# STM32_learning_stand.net
KiCad netlist of a schematic drawn in EAGLE
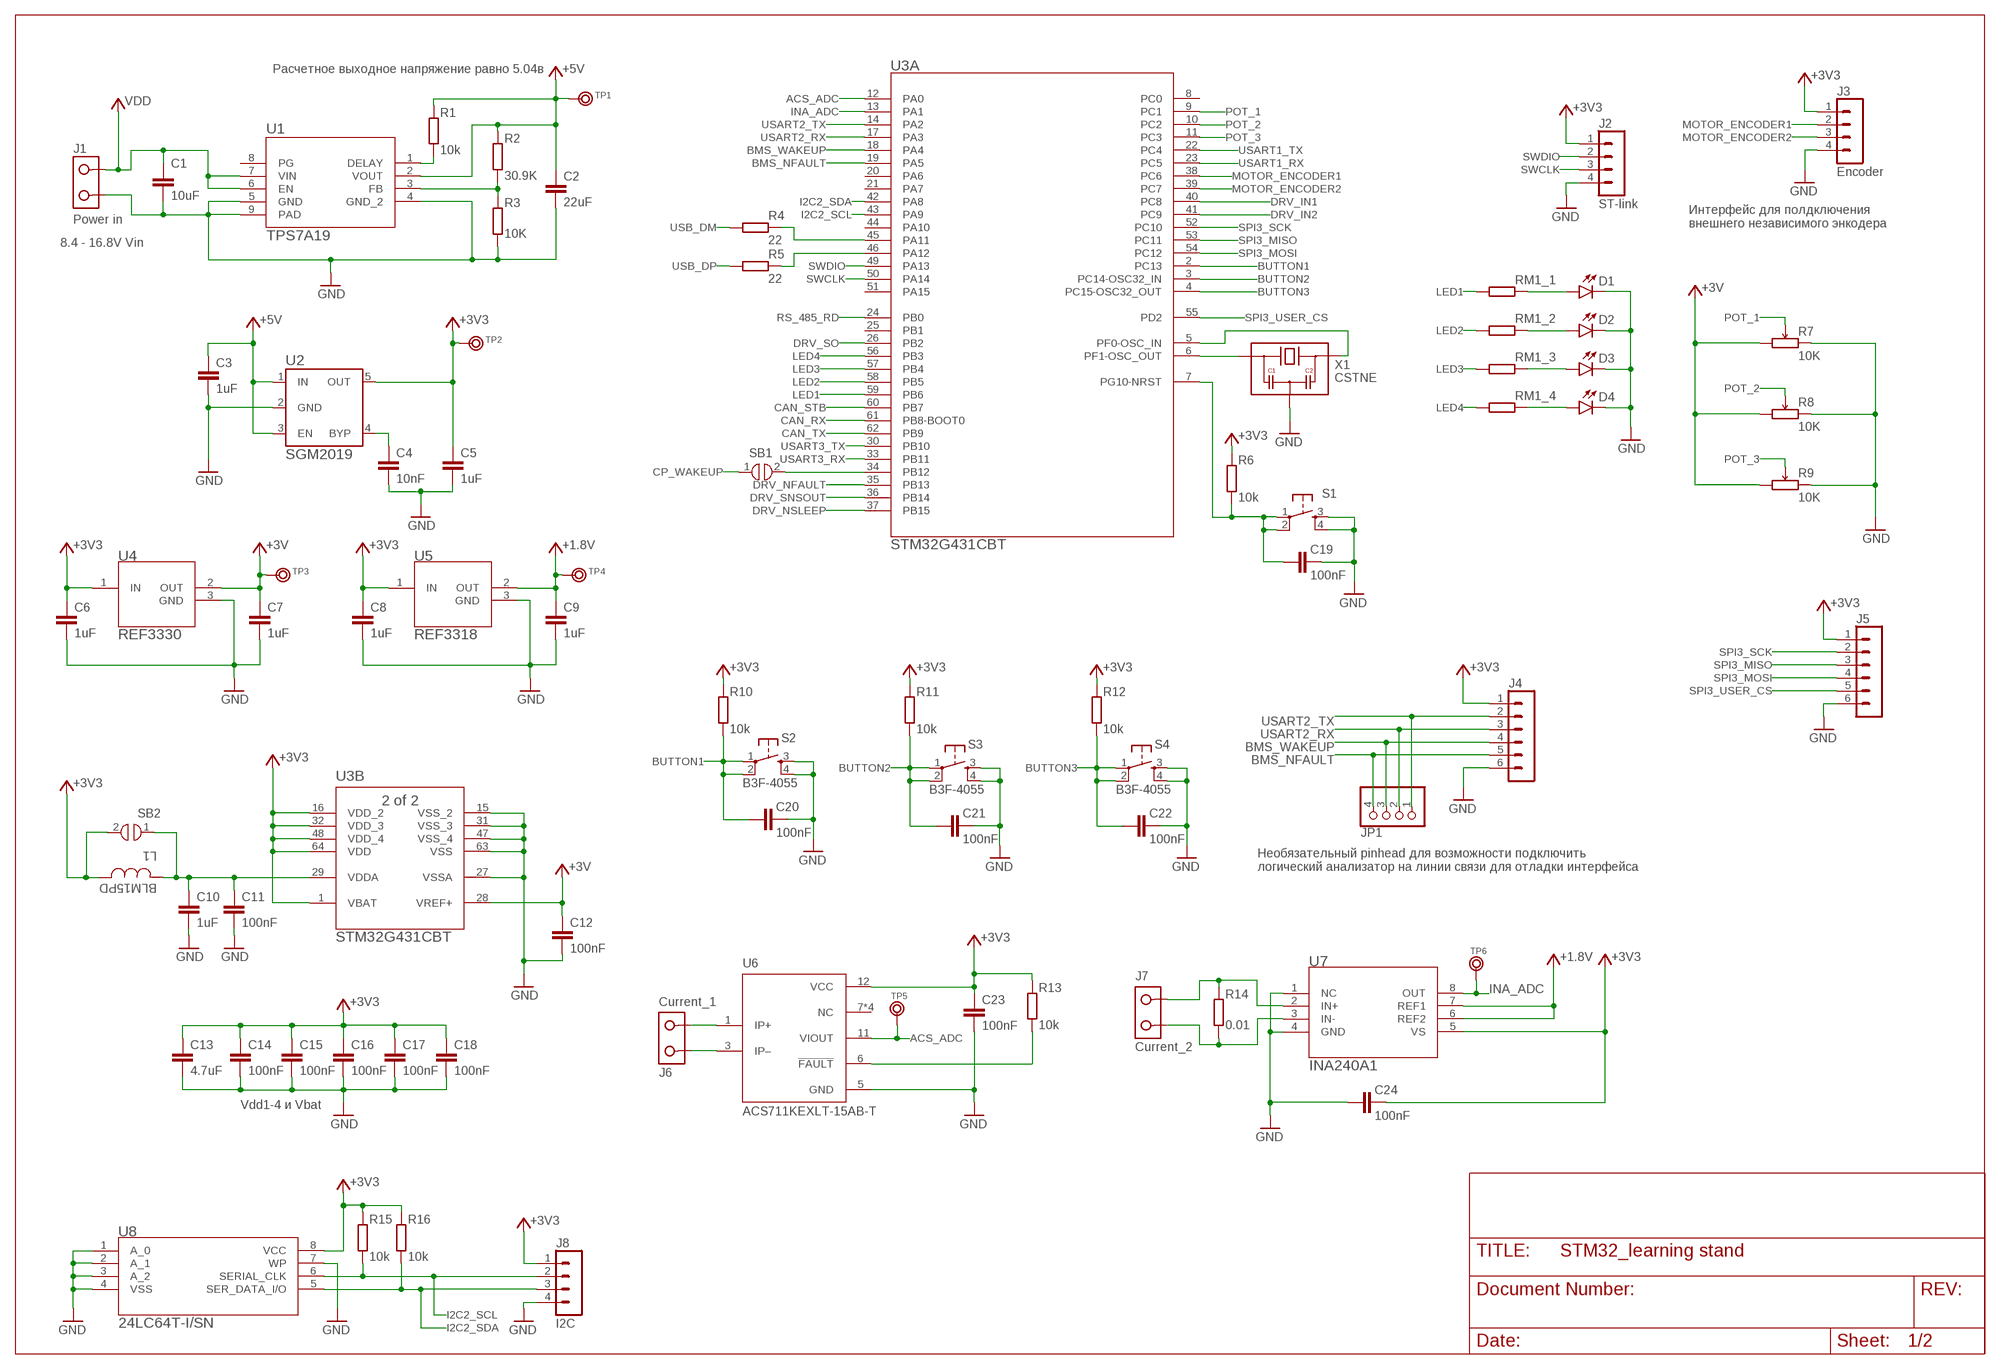
[diagram p0: schematic, sheet 1]
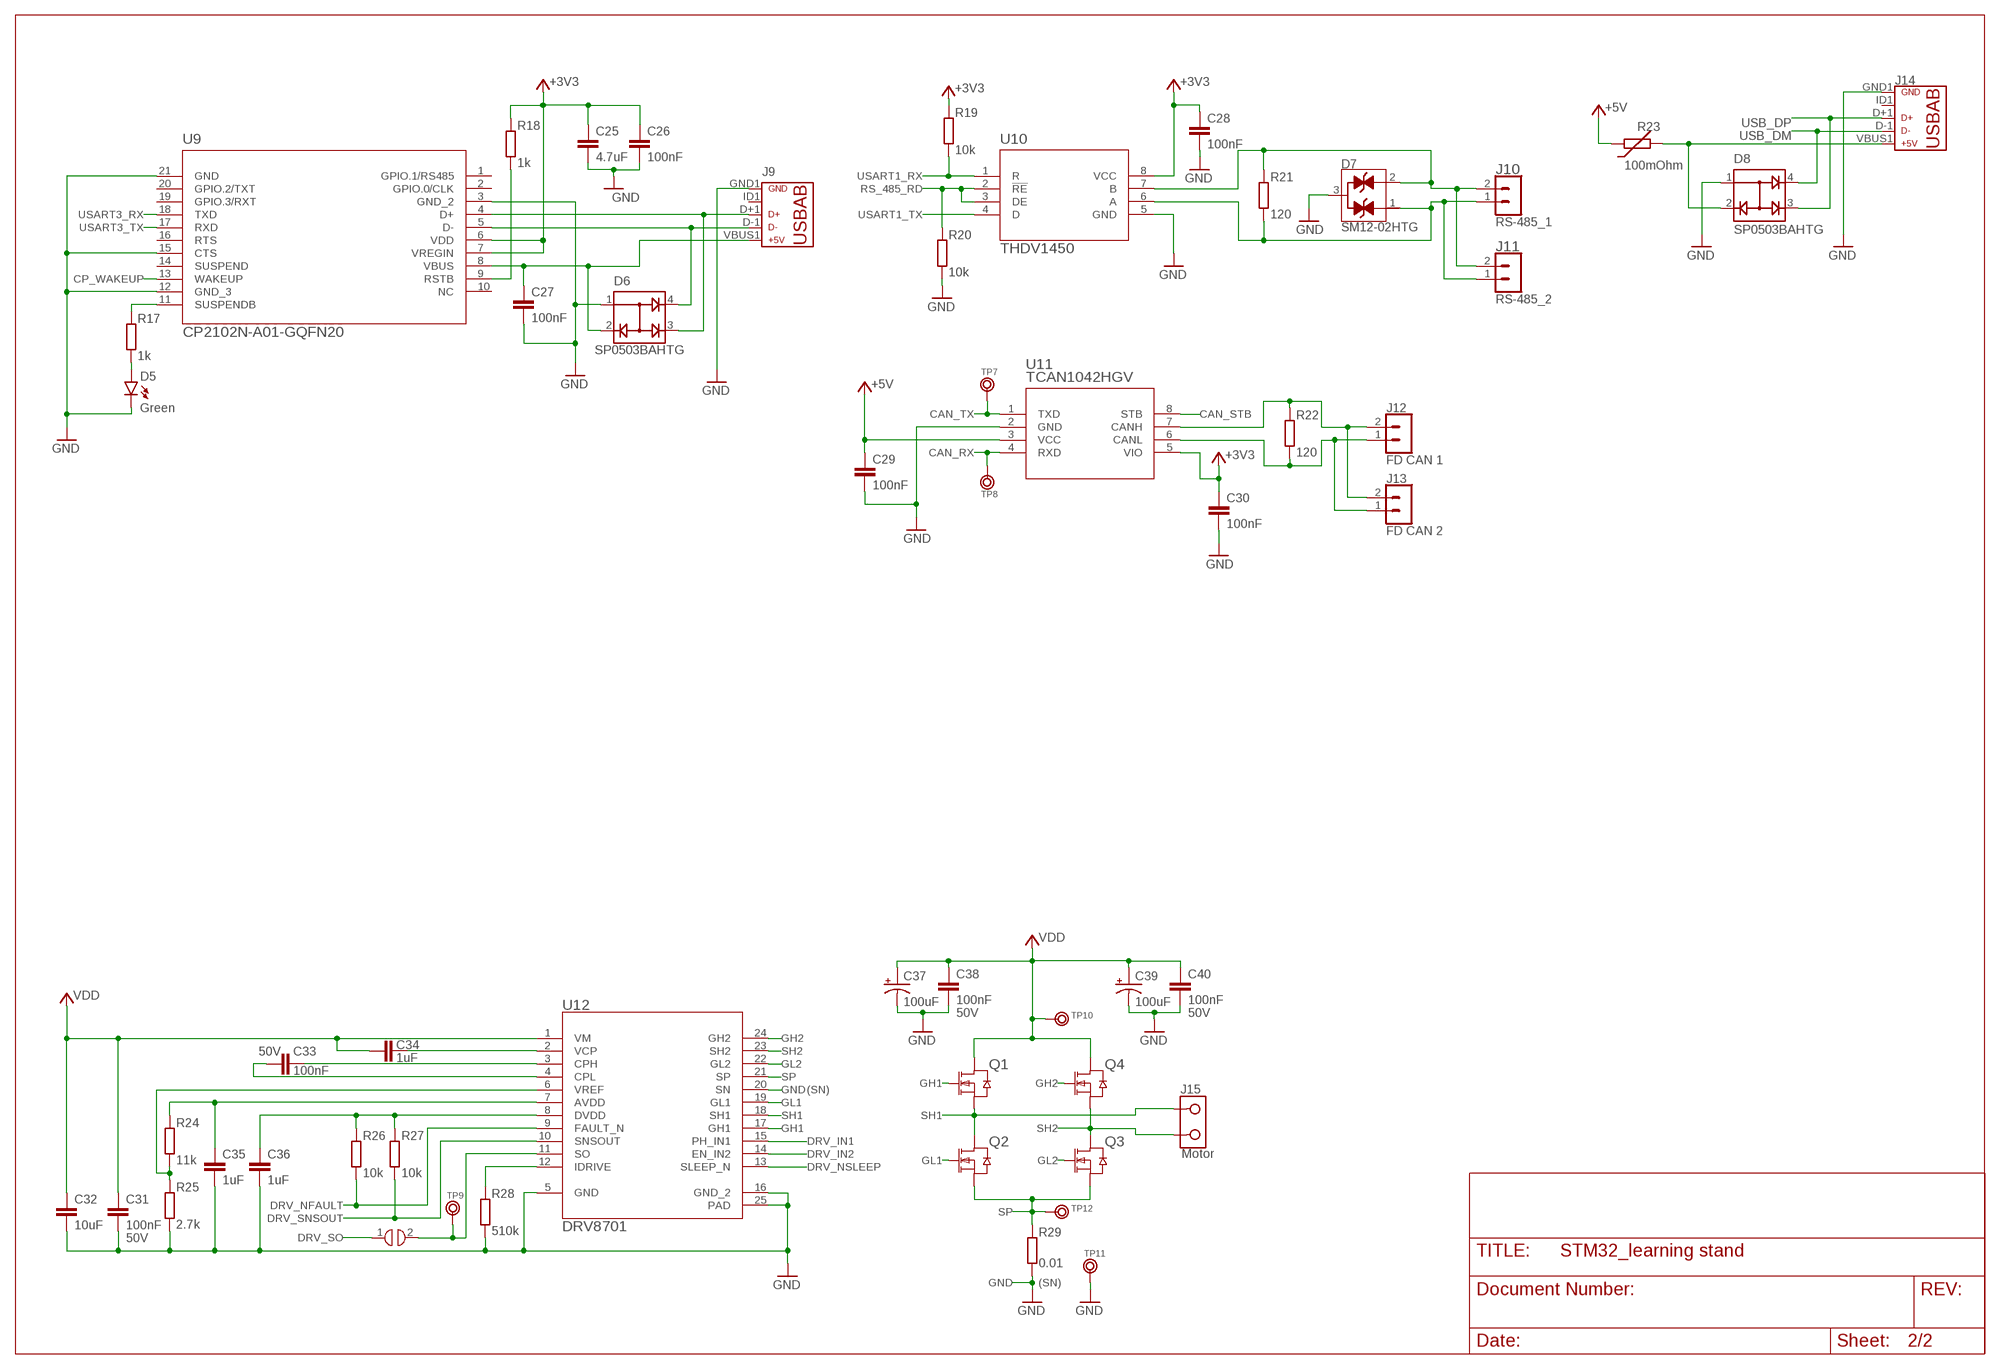
[diagram p1: schematic, sheet 2]

(export (version "E")
  (design (tool "Eeschema 10.0.6"))
  (components
    (comp (ref "C25")
      (value "4.7uF")
      (footprint "eagle-import:C0603")
      (libsource (lib "eagle-import") (part "C-EU0603"))
    )
    (comp (ref "C26")
      (value "100nF")
      (footprint "eagle-import:C0402")
      (libsource (lib "eagle-import") (part "C-EU0402"))
    )
    (comp (ref "C27")
      (value "100nF")
      (footprint "eagle-import:C0402")
      (libsource (lib "eagle-import") (part "C-EU0402"))
    )
    (comp (ref "C28")
      (value "100nF")
      (footprint "eagle-import:C0402")
      (libsource (lib "eagle-import") (part "C-EU0402"))
    )
    (comp (ref "C29")
      (value "100nF")
      (footprint "eagle-import:C0402")
      (libsource (lib "eagle-import") (part "C-EU0402"))
    )
    (comp (ref "C30")
      (value "100nF")
      (footprint "eagle-import:C0402")
      (libsource (lib "eagle-import") (part "C-EU0402"))
    )
    (comp (ref "C31")
      (value "100nF")
      (footprint "eagle-import:C0603")
      (libsource (lib "eagle-import") (part "C-EU-CERAMIC0603"))
    )
    (comp (ref "C32")
      (value "10uF")
      (footprint "eagle-import:C1206")
      (libsource (lib "eagle-import") (part "C-EU1206"))
    )
    (comp (ref "C33")
      (value "100nF")
      (footprint "eagle-import:C0603")
      (libsource (lib "eagle-import") (part "C-EU-CERAMIC0603"))
    )
    (comp (ref "C34")
      (value "1uF")
      (footprint "eagle-import:C0603")
      (libsource (lib "eagle-import") (part "C-EU0603"))
    )
    (comp (ref "C35")
      (value "1uF")
      (footprint "eagle-import:C0603")
      (libsource (lib "eagle-import") (part "C-EU0603"))
    )
    (comp (ref "C36")
      (value "1uF")
      (footprint "eagle-import:C0603")
      (libsource (lib "eagle-import") (part "C-EU0603"))
    )
    (comp (ref "C37")
      (value "100uF")
      (footprint "eagle-import:6.3X7.7")
      (fields
        (field (name "MANUFACTURER_PART_NUMBER") "EEE-1VA100WAR")
        (field (name "COPYRIGHT") "Copyright (C) 2018 Accelerated Designs. All rights reserved")
      )
      (libsource (lib "eagle-import") (part "C-EU-ELECTROLYTIC-6.3X7.7"))
    )
    (comp (ref "C38")
      (value "100nF")
      (footprint "eagle-import:C0603")
      (libsource (lib "eagle-import") (part "C-EU-CERAMIC0603"))
    )
    (comp (ref "C39")
      (value "100uF")
      (footprint "eagle-import:6.3X7.7")
      (fields
        (field (name "MANUFACTURER_PART_NUMBER") "EEE-1VA100WAR")
        (field (name "COPYRIGHT") "Copyright (C) 2018 Accelerated Designs. All rights reserved")
      )
      (libsource (lib "eagle-import") (part "C-EU-ELECTROLYTIC-6.3X7.7"))
    )
    (comp (ref "C40")
      (value "100nF")
      (footprint "eagle-import:C0603")
      (libsource (lib "eagle-import") (part "C-EU-CERAMIC0603"))
    )
    (comp (ref "D5")
      (value "Green")
      (footprint "eagle-import:LED-0805")
      (libsource (lib "eagle-import") (part "LED0805"))
    )
    (comp (ref "D6")
      (value "SP0503BAHTG")
      (footprint "eagle-import:SOT143")
      (fields (field (name "DIGI-KEY_PART_NUMBER") "F2715CT-ND") (field (name "MF") "Littelfuse Inc."))
      (libsource (lib "eagle-import") (part "SP0503BAHTG"))
    )
    (comp (ref "D7")
      (value "SM12-02HTG")
      (footprint "eagle-import:SOT23")
      (libsource (lib "eagle-import") (part "SOT_23_TVS"))
    )
    (comp (ref "D8")
      (value "SP0503BAHTG")
      (footprint "eagle-import:SOT143")
      (fields (field (name "DIGI-KEY_PART_NUMBER") "F2715CT-ND") (field (name "MF") "Littelfuse Inc."))
      (libsource (lib "eagle-import") (part "SP0503BAHTG"))
    )
    (comp (ref "J9")
      (value "USB_MICRO\"\"")
      (footprint "eagle-import:USB-MICRO-SMD")
      (libsource (lib "eagle-import") (part "USB_MICRO{dblquote}{dblquote}"))
    )
    (comp (ref "J10")
      (value "RS-485_1")
      (footprint "eagle-import:S2B-PH-K")
      (libsource (lib "eagle-import") (part "S2B-PH-K"))
    )
    (comp (ref "J11")
      (value "RS-485_2")
      (footprint "eagle-import:S2B-PH-K")
      (libsource (lib "eagle-import") (part "S2B-PH-K"))
    )
    (comp (ref "J12")
      (value "FD CAN 1")
      (footprint "eagle-import:S2B-PH-K")
      (libsource (lib "eagle-import") (part "S2B-PH-K"))
    )
    (comp (ref "J13")
      (value "FD CAN 2")
      (footprint "eagle-import:S2B-PH-K")
      (libsource (lib "eagle-import") (part "S2B-PH-K"))
    )
    (comp (ref "J14")
      (value "USB_MICRO\"\"")
      (footprint "eagle-import:USB-MICRO-SMD")
      (libsource (lib "eagle-import") (part "USB_MICRO{dblquote}{dblquote}"))
    )
    (comp (ref "J15")
      (value "Motor")
      (footprint "eagle-import:DG301-2P")
      (libsource (lib "eagle-import") (part "DG301-2P{dblquote}"))
    )
    (comp (ref "Q1")
      (value "SON5X6_MOSFET")
      (footprint "eagle-import:SON5X6")
      (fields (field (name "MANUFACTURER_PART_NUMBER") "CSD18534Q5A"))
      (libsource (lib "eagle-import") (part "SON5X6_MOSFET"))
    )
    (comp (ref "Q2")
      (value "SON5X6_MOSFET")
      (footprint "eagle-import:SON5X6")
      (fields (field (name "MANUFACTURER_PART_NUMBER") "CSD18534Q5A"))
      (libsource (lib "eagle-import") (part "SON5X6_MOSFET"))
    )
    (comp (ref "Q3")
      (value "SON5X6_MOSFET")
      (footprint "eagle-import:SON5X6")
      (fields (field (name "MANUFACTURER_PART_NUMBER") "CSD18534Q5A"))
      (libsource (lib "eagle-import") (part "SON5X6_MOSFET"))
    )
    (comp (ref "Q4")
      (value "SON5X6_MOSFET")
      (footprint "eagle-import:SON5X6")
      (fields (field (name "MANUFACTURER_PART_NUMBER") "CSD18534Q5A"))
      (libsource (lib "eagle-import") (part "SON5X6_MOSFET"))
    )
    (comp (ref "R17")
      (value "1k")
      (footprint "eagle-import:R0402")
      (libsource (lib "eagle-import") (part "R-EU0402"))
    )
    (comp (ref "R18")
      (value "1k")
      (footprint "eagle-import:R0402")
      (libsource (lib "eagle-import") (part "R-EU0402"))
    )
    (comp (ref "R19")
      (value "10k")
      (footprint "eagle-import:R0402")
      (libsource (lib "eagle-import") (part "R-EU0402"))
    )
    (comp (ref "R20")
      (value "10k")
      (footprint "eagle-import:R0402")
      (libsource (lib "eagle-import") (part "R-EU0402"))
    )
    (comp (ref "R21")
      (value "120")
      (footprint "eagle-import:R0805")
      (libsource (lib "eagle-import") (part "R-EU0805"))
    )
    (comp (ref "R22")
      (value "120")
      (footprint "eagle-import:R0805")
      (libsource (lib "eagle-import") (part "R-EU0805"))
    )
    (comp (ref "R23")
      (value "100mOhm")
      (footprint "eagle-import:0805_PTC_FUSE")
      (libsource (lib "eagle-import") (part "PTC_FUSE-0805"))
    )
    (comp (ref "R24")
      (value "11k")
      (footprint "eagle-import:R0402")
      (libsource (lib "eagle-import") (part "R-EU0402"))
    )
    (comp (ref "R25")
      (value "2.7k")
      (footprint "eagle-import:R0402")
      (libsource (lib "eagle-import") (part "R-EU0402"))
    )
    (comp (ref "R26")
      (value "10k")
      (footprint "eagle-import:R0402")
      (libsource (lib "eagle-import") (part "R-EU0402"))
    )
    (comp (ref "R27")
      (value "10k")
      (footprint "eagle-import:R0402")
      (libsource (lib "eagle-import") (part "R-EU0402"))
    )
    (comp (ref "R28")
      (value "510k")
      (footprint "eagle-import:R0402")
      (libsource (lib "eagle-import") (part "R-EU0402"))
    )
    (comp (ref "R29")
      (value "0.01")
      (footprint "eagle-import:CS_R0805")
      (libsource (lib "eagle-import") (part "R_EU_CS"))
    )
    (comp (ref "SB3")
      (value "SOLDER_BRIDGE")
      (footprint "eagle-import:SOLDER_BRIDGE")
      (libsource (lib "eagle-import") (part "SOLDER_BRIDGE"))
    )
    (comp (ref "TP7")
      (value "TEST_RING")
      (footprint "eagle-import:TEST_RING")
      (libsource (lib "eagle-import") (part "TEST_RING"))
    )
    (comp (ref "TP8")
      (value "TEST_RING")
      (footprint "eagle-import:TEST_RING")
      (libsource (lib "eagle-import") (part "TEST_RING"))
    )
    (comp (ref "TP9")
      (value "TEST_RING")
      (footprint "eagle-import:TEST_RING")
      (libsource (lib "eagle-import") (part "TEST_RING"))
    )
    (comp (ref "TP10")
      (value "TEST_RING")
      (footprint "eagle-import:TEST_RING")
      (libsource (lib "eagle-import") (part "TEST_RING"))
    )
    (comp (ref "TP11")
      (value "TEST_RING")
      (footprint "eagle-import:TEST_RING")
      (libsource (lib "eagle-import") (part "TEST_RING"))
    )
    (comp (ref "TP12")
      (value "TEST_RING")
      (footprint "eagle-import:TEST_RING")
      (libsource (lib "eagle-import") (part "TEST_RING"))
    )
    (comp (ref "U9")
      (value "CP2102N-A01-GQFN20")
      (footprint "eagle-import:QFN20C_3X3")
      (fields (field (name "COPYRIGHT") "Copyright (C) 2016 Accelerated Designs. All rights reserved"))
      (libsource (lib "eagle-import") (part "CP2102N-A01-GQFN20"))
    )
    (comp (ref "U10")
      (value "THDV1450")
      (footprint "eagle-import:SOIC8")
      (libsource (lib "eagle-import") (part "RS485_S8"))
    )
    (comp (ref "U11")
      (value "TCAN1042HGV")
      (footprint "eagle-import:SOIC_8")
      (libsource (lib "eagle-import") (part "8_PIN_CAN_TRANSIVERSTB_VIO"))
    )
    (comp (ref "U12")
      (value "DRV8701")
      (footprint "eagle-import:VQFN-24")
      (libsource (lib "eagle-import") (part "DRV8701"))
    )
    (comp (ref "C1")
      (value "10uF")
      (footprint "eagle-import:C1206")
      (libsource (lib "eagle-import") (part "C-EU1206"))
    )
    (comp (ref "C2")
      (value "22uF")
      (footprint "eagle-import:C0805")
      (libsource (lib "eagle-import") (part "C-EU0805"))
    )
    (comp (ref "C3")
      (value "1uF")
      (footprint "eagle-import:C0603")
      (libsource (lib "eagle-import") (part "C-EU0603"))
    )
    (comp (ref "C4")
      (value "10nF")
      (footprint "eagle-import:C0402")
      (libsource (lib "eagle-import") (part "C-EU0402"))
    )
    (comp (ref "C5")
      (value "1uF")
      (footprint "eagle-import:C0603")
      (libsource (lib "eagle-import") (part "C-EU0603"))
    )
    (comp (ref "C6")
      (value "1uF")
      (footprint "eagle-import:C0603")
      (libsource (lib "eagle-import") (part "C-EU0603"))
    )
    (comp (ref "C7")
      (value "1uF")
      (footprint "eagle-import:C0603")
      (libsource (lib "eagle-import") (part "C-EU0603"))
    )
    (comp (ref "C8")
      (value "1uF")
      (footprint "eagle-import:C0603")
      (libsource (lib "eagle-import") (part "C-EU0603"))
    )
    (comp (ref "C9")
      (value "1uF")
      (footprint "eagle-import:C0603")
      (libsource (lib "eagle-import") (part "C-EU0603"))
    )
    (comp (ref "C10")
      (value "1uF")
      (footprint "eagle-import:C0603")
      (libsource (lib "eagle-import") (part "C-EU0603"))
    )
    (comp (ref "C11")
      (value "100nF")
      (footprint "eagle-import:C0402")
      (libsource (lib "eagle-import") (part "C-EU0402"))
    )
    (comp (ref "C12")
      (value "100nF")
      (footprint "eagle-import:C0402")
      (libsource (lib "eagle-import") (part "C-EU0402"))
    )
    (comp (ref "C13")
      (value "4.7uF")
      (footprint "eagle-import:C0603")
      (libsource (lib "eagle-import") (part "C-EU0603"))
    )
    (comp (ref "C14")
      (value "100nF")
      (footprint "eagle-import:C0402")
      (libsource (lib "eagle-import") (part "C-EU0402"))
    )
    (comp (ref "C15")
      (value "100nF")
      (footprint "eagle-import:C0402")
      (libsource (lib "eagle-import") (part "C-EU0402"))
    )
    (comp (ref "C16")
      (value "100nF")
      (footprint "eagle-import:C0402")
      (libsource (lib "eagle-import") (part "C-EU0402"))
    )
    (comp (ref "C17")
      (value "100nF")
      (footprint "eagle-import:C0402")
      (libsource (lib "eagle-import") (part "C-EU0402"))
    )
    (comp (ref "C18")
      (value "100nF")
      (footprint "eagle-import:C0402")
      (libsource (lib "eagle-import") (part "C-EU0402"))
    )
    (comp (ref "C19")
      (value "100nF")
      (footprint "eagle-import:C0402")
      (libsource (lib "eagle-import") (part "C-EU0402"))
    )
    (comp (ref "C20")
      (value "100nF")
      (footprint "eagle-import:C0402")
      (libsource (lib "eagle-import") (part "C-EU0402"))
    )
    (comp (ref "C21")
      (value "100nF")
      (footprint "eagle-import:C0402")
      (libsource (lib "eagle-import") (part "C-EU0402"))
    )
    (comp (ref "C22")
      (value "100nF")
      (footprint "eagle-import:C0402")
      (libsource (lib "eagle-import") (part "C-EU0402"))
    )
    (comp (ref "C23")
      (value "100nF")
      (footprint "eagle-import:C0402")
      (libsource (lib "eagle-import") (part "C-EU0402"))
    )
    (comp (ref "C24")
      (value "100nF")
      (footprint "eagle-import:C0402")
      (libsource (lib "eagle-import") (part "C-EU0402"))
    )
    (comp (ref "D1")
      (value "Blue")
      (footprint "eagle-import:LED-0805")
      (libsource (lib "eagle-import") (part "LED0805"))
    )
    (comp (ref "D2")
      (value "Blue")
      (footprint "eagle-import:LED-0805")
      (libsource (lib "eagle-import") (part "LED0805"))
    )
    (comp (ref "D3")
      (value "Blue")
      (footprint "eagle-import:LED-0805")
      (libsource (lib "eagle-import") (part "LED0805"))
    )
    (comp (ref "D4")
      (value "Blue")
      (footprint "eagle-import:LED-0805")
      (libsource (lib "eagle-import") (part "LED0805"))
    )
    (comp (ref "J1")
      (value "Power in")
      (footprint "eagle-import:DG301-2P")
      (libsource (lib "eagle-import") (part "DG301-2P{dblquote}"))
    )
    (comp (ref "J2")
      (value "ST-link")
      (footprint "eagle-import:S4B-PH-K")
      (libsource (lib "eagle-import") (part "S4B-PH-K"))
    )
    (comp (ref "J3")
      (value "Encoder")
      (footprint "eagle-import:S4B-PH-K")
      (libsource (lib "eagle-import") (part "S4B-PH-K"))
    )
    (comp (ref "J4")
      (value "BMS_interface")
      (footprint "eagle-import:S6B-PH-K")
      (libsource (lib "eagle-import") (part "S6B-PH-K"))
    )
    (comp (ref "J5")
      (value "S6B-PH-K")
      (footprint "eagle-import:S6B-PH-K")
      (libsource (lib "eagle-import") (part "S6B-PH-K"))
    )
    (comp (ref "J6")
      (value "Current_1")
      (footprint "eagle-import:DG301-2P")
      (libsource (lib "eagle-import") (part "DG301-2P{dblquote}"))
    )
    (comp (ref "J7")
      (value "Current_2")
      (footprint "eagle-import:DG301-2P")
      (libsource (lib "eagle-import") (part "DG301-2P{dblquote}"))
    )
    (comp (ref "J8")
      (value "I2C")
      (footprint "eagle-import:B4B-PH-K")
      (libsource (lib "eagle-import") (part "B4B-PH-K"))
    )
    (comp (ref "JP1")
      (value "PINHD-1X4")
      (footprint "eagle-import:1X04")
      (libsource (lib "eagle-import") (part "PINHD-1X4"))
    )
    (comp (ref "L1")
      (value "BLM15PD")
      (footprint "eagle-import:0402")
      (fields (field (name "MANUFACTURER_PART_NUMBER") "BLM15PD121SN1D"))
      (libsource (lib "eagle-import") (part "0402"))
    )
    (comp (ref "R1")
      (value "10k")
      (footprint "eagle-import:R0402")
      (libsource (lib "eagle-import") (part "R-EU0402"))
    )
    (comp (ref "R2")
      (value "30.9K")
      (footprint "eagle-import:R0603")
      (libsource (lib "eagle-import") (part "R-EU0603"))
    )
    (comp (ref "R3")
      (value "10K")
      (footprint "eagle-import:R0603")
      (libsource (lib "eagle-import") (part "R-EU0603"))
    )
    (comp (ref "R4")
      (value "22")
      (footprint "eagle-import:R0402")
      (libsource (lib "eagle-import") (part "R-EU0402"))
    )
    (comp (ref "R5")
      (value "22")
      (footprint "eagle-import:R0402")
      (libsource (lib "eagle-import") (part "R-EU0402"))
    )
    (comp (ref "R6")
      (value "10k")
      (footprint "eagle-import:R0402")
      (libsource (lib "eagle-import") (part "R-EU0402"))
    )
    (comp (ref "R7")
      (value "10K")
      (footprint "eagle-import:ALPS_PTM")
      (libsource (lib "eagle-import") (part "POTEMTIOMETER_EU"))
    )
    (comp (ref "R8")
      (value "10K")
      (footprint "eagle-import:ALPS_PTM")
      (libsource (lib "eagle-import") (part "POTEMTIOMETER_EU"))
    )
    (comp (ref "R9")
      (value "10K")
      (footprint "eagle-import:ALPS_PTM")
      (libsource (lib "eagle-import") (part "POTEMTIOMETER_EU"))
    )
    (comp (ref "R10")
      (value "10k")
      (footprint "eagle-import:R0402")
      (libsource (lib "eagle-import") (part "R-EU0402"))
    )
    (comp (ref "R11")
      (value "10k")
      (footprint "eagle-import:R0402")
      (libsource (lib "eagle-import") (part "R-EU0402"))
    )
    (comp (ref "R12")
      (value "10k")
      (footprint "eagle-import:R0402")
      (libsource (lib "eagle-import") (part "R-EU0402"))
    )
    (comp (ref "R13")
      (value "10k")
      (footprint "eagle-import:R0402")
      (libsource (lib "eagle-import") (part "R-EU0402"))
    )
    (comp (ref "R14")
      (value "0.01")
      (footprint "eagle-import:CS_R0805")
      (libsource (lib "eagle-import") (part "R_EU_CS"))
    )
    (comp (ref "R15")
      (value "10k")
      (footprint "eagle-import:R0402")
      (libsource (lib "eagle-import") (part "R-EU0402"))
    )
    (comp (ref "R16")
      (value "10k")
      (footprint "eagle-import:R0402")
      (libsource (lib "eagle-import") (part "R-EU0402"))
    )
    (comp (ref "RM1")
      (value "RES_ARRAY")
      (footprint "eagle-import:0603-ARC")
      (libsource (lib "eagle-import") (part "RES_ARRAY"))
    )
    (comp (ref "S1")
      (value "MOMENTARY-SWITCH-SPST-2-[SMD-5.2MM]")
      (footprint "eagle-import:TACTILE_SWITCH_SMD_5.2MM")
      (libsource (lib "eagle-import") (part "MOMENTARY-SWITCH-SPST-2-[SMD-5.2MM]"))
    )
    (comp (ref "S2")
      (value "B3F-4055")
      (footprint "eagle-import:SWITCH_B3F-4055")
      (fields (field (name "COPYRIGHT") "Copyright (C) 2018 Accelerated Designs. All rights reserved"))
      (libsource (lib "eagle-import") (part "B3F-4055"))
    )
    (comp (ref "S3")
      (value "B3F-4055")
      (footprint "eagle-import:SWITCH_B3F-4055")
      (fields (field (name "COPYRIGHT") "Copyright (C) 2018 Accelerated Designs. All rights reserved"))
      (libsource (lib "eagle-import") (part "B3F-4055"))
    )
    (comp (ref "S4")
      (value "B3F-4055")
      (footprint "eagle-import:SWITCH_B3F-4055")
      (fields (field (name "COPYRIGHT") "Copyright (C) 2018 Accelerated Designs. All rights reserved"))
      (libsource (lib "eagle-import") (part "B3F-4055"))
    )
    (comp (ref "SB1")
      (value "SOLDER_BRIDGE")
      (footprint "eagle-import:SOLDER_BRIDGE")
      (libsource (lib "eagle-import") (part "SOLDER_BRIDGE"))
    )
    (comp (ref "SB2")
      (value "SOLDER_BRIDGE")
      (footprint "eagle-import:SOLDER_BRIDGE")
      (libsource (lib "eagle-import") (part "SOLDER_BRIDGE"))
    )
    (comp (ref "TP1")
      (value "TEST_RING")
      (footprint "eagle-import:TEST_RING")
      (libsource (lib "eagle-import") (part "TEST_RING"))
    )
    (comp (ref "TP2")
      (value "TEST_RING")
      (footprint "eagle-import:TEST_RING")
      (libsource (lib "eagle-import") (part "TEST_RING"))
    )
    (comp (ref "TP3")
      (value "TEST_RING")
      (footprint "eagle-import:TEST_RING")
      (libsource (lib "eagle-import") (part "TEST_RING"))
    )
    (comp (ref "TP4")
      (value "TEST_RING")
      (footprint "eagle-import:TEST_RING")
      (libsource (lib "eagle-import") (part "TEST_RING"))
    )
    (comp (ref "TP5")
      (value "TEST_RING")
      (footprint "eagle-import:TEST_RING")
      (libsource (lib "eagle-import") (part "TEST_RING"))
    )
    (comp (ref "TP6")
      (value "TEST_RING")
      (footprint "eagle-import:TEST_RING")
      (libsource (lib "eagle-import") (part "TEST_RING"))
    )
    (comp (ref "U1")
      (value "TPS7A19")
      (footprint "eagle-import:DRB0008B")
      (fields
        (field (name "MANUFACTURER_PART_NUMBER") "TPS7A1901DRBT")
        (field (name "COPYRIGHT") "Copyright (C) 2018 Accelerated Designs. All rights reserved")
      )
      (libsource (lib "eagle-import") (part "TPS7A1901DRBT"))
    )
    (comp (ref "U2")
      (value "SGM2019")
      (footprint "eagle-import:SOT23-5")
      (libsource (lib "eagle-import") (part "SGM2019"))
    )
    (comp (ref "U3")
      (value "STM32G431CBT")
      (footprint "eagle-import:LQFP64-10X10MM")
      (fields
        (field (name "MANUFACTURER_PART_NUMBER") "STM32G4_LQFP64_T1")
        (field (name "COPYRIGHT") "Copyright (C) 2016 Accelerated Designs. All rights reserved")
      )
      (libsource (lib "eagle-import") (part "STM32G4_LQFP64"))
    )
    (comp (ref "U4")
      (value "REF3330")
      (footprint "eagle-import:SOT-23-3")
      (fields
        (field (name "MANUFACTURER") "Texas Instruments")
        (field (name "MANUFACTURER_PART_NUMBER") "REF3318AIDCKR")
      )
      (libsource (lib "eagle-import") (part "REF33"))
    )
    (comp (ref "U5")
      (value "REF3318")
      (footprint "eagle-import:SOT-23-3")
      (fields
        (field (name "MANUFACTURER") "Texas Instruments")
        (field (name "MANUFACTURER_PART_NUMBER") "REF3318AIDCKR")
      )
      (libsource (lib "eagle-import") (part "REF33"))
    )
    (comp (ref "U6")
      (value "ACS711KEXLT-15AB-T")
      (footprint "eagle-import:SENSOR_ACS711KEXLT-15AB-T")
      (fields (field (name "MF") "Allegro MicroSystems LLC"))
      (libsource (lib "eagle-import") (part "ACS711KEXLT-15AB-T"))
    )
    (comp (ref "U7")
      (value "INA240A1")
      (footprint "eagle-import:TSSOP-8")
      (libsource (lib "eagle-import") (part "INA240_TSSOP"))
    )
    (comp (ref "U8")
      (value "24LC64T-I/SN")
      (footprint "eagle-import:SOIC8")
      (libsource (lib "eagle-import") (part "SOIC8_I2C_SMALL"))
    )
    (comp (ref "X1")
      (value "CSTNE")
      (footprint "eagle-import:MURATA_SMD_3P")
      (libsource (lib "eagle-import") (part "CSTNE"))
    )
  )
  (nets
    (net (code "1") (name "+1.8V") (class "Default")
      (node (ref "C9") (pin "2") (pinfunction "2_2") (pintype "passive"))
      (node (ref "TP4") (pin "1") (pinfunction "P$1_1") (pintype "bidirectional"))
      (node (ref "U5") (pin "2") (pinfunction "OUT_2") (pintype "output"))
      (node (ref "U7") (pin "6") (pinfunction "REF2_6") (pintype "input"))
      (node (ref "U7") (pin "7") (pinfunction "REF1_7") (pintype "input"))
    )
    (net (code "2") (name "+3V") (class "Default")
      (node (ref "C12") (pin "1") (pinfunction "1_1") (pintype "passive"))
      (node (ref "C7") (pin "2") (pinfunction "2_2") (pintype "passive"))
      (node (ref "R7") (pin "P$1") (pinfunction "1_P$1") (pintype "passive"))
      (node (ref "R8") (pin "P$1") (pinfunction "1_P$1") (pintype "passive"))
      (node (ref "R9") (pin "P$1") (pinfunction "1_P$1") (pintype "passive"))
      (node (ref "TP3") (pin "1") (pinfunction "P$1_1") (pintype "bidirectional"))
      (node (ref "U3") (pin "28") (pinfunction "VREF+_28") (pintype "power_in"))
      (node (ref "U4") (pin "2") (pinfunction "OUT_2") (pintype "output"))
    )
    (net (code "3") (name "+3V3") (class "Default")
      (node (ref "C13") (pin "2") (pinfunction "2_2") (pintype "passive"))
      (node (ref "C14") (pin "1") (pinfunction "1_1") (pintype "passive"))
      (node (ref "C15") (pin "1") (pinfunction "1_1") (pintype "passive"))
      (node (ref "C16") (pin "1") (pinfunction "1_1") (pintype "passive"))
      (node (ref "C17") (pin "1") (pinfunction "1_1") (pintype "passive"))
      (node (ref "C18") (pin "1") (pinfunction "1_1") (pintype "passive"))
      (node (ref "C23") (pin "1") (pinfunction "1_1") (pintype "passive"))
      (node (ref "C24") (pin "2") (pinfunction "2_2") (pintype "passive"))
      (node (ref "C25") (pin "2") (pinfunction "2_2") (pintype "passive"))
      (node (ref "C26") (pin "1") (pinfunction "1_1") (pintype "passive"))
      (node (ref "C28") (pin "1") (pinfunction "1_1") (pintype "passive"))
      (node (ref "C30") (pin "1") (pinfunction "1_1") (pintype "passive"))
      (node (ref "C5") (pin "2") (pinfunction "2_2") (pintype "passive"))
      (node (ref "C6") (pin "2") (pinfunction "2_2") (pintype "passive"))
      (node (ref "C8") (pin "2") (pinfunction "2_2") (pintype "passive"))
      (node (ref "J2") (pin "1") (pinfunction "1_1") (pintype "passive"))
      (node (ref "J3") (pin "1") (pinfunction "1_1") (pintype "passive"))
      (node (ref "J4") (pin "1") (pinfunction "1_1") (pintype "passive"))
      (node (ref "J5") (pin "1") (pinfunction "1_1") (pintype "passive"))
      (node (ref "J8") (pin "1") (pinfunction "1_1") (pintype "passive"))
      (node (ref "L1") (pin "2") (pinfunction "2_2") (pintype "passive"))
      (node (ref "R10") (pin "2") (pinfunction "2_2") (pintype "passive"))
      (node (ref "R11") (pin "2") (pinfunction "2_2") (pintype "passive"))
      (node (ref "R12") (pin "2") (pinfunction "2_2") (pintype "passive"))
      (node (ref "R13") (pin "2") (pinfunction "2_2") (pintype "passive"))
      (node (ref "R15") (pin "2") (pinfunction "2_2") (pintype "passive"))
      (node (ref "R16") (pin "2") (pinfunction "2_2") (pintype "passive"))
      (node (ref "R18") (pin "2") (pinfunction "2_2") (pintype "passive"))
      (node (ref "R19") (pin "2") (pinfunction "2_2") (pintype "passive"))
      (node (ref "R6") (pin "2") (pinfunction "2_2") (pintype "passive"))
      (node (ref "SB2") (pin "2") (pinfunction "2_2") (pintype "passive"))
      (node (ref "TP2") (pin "1") (pinfunction "P$1_1") (pintype "bidirectional"))
      (node (ref "U10") (pin "8") (pinfunction "VCC_8") (pintype "power_in"))
      (node (ref "U11") (pin "5") (pinfunction "VIO_5") (pintype "power_in"))
      (node (ref "U2") (pin "5") (pinfunction "OUT_5") (pintype "output"))
      (node (ref "U3") (pin "1") (pinfunction "VBAT_1") (pintype "power_in"))
      (node (ref "U3") (pin "16") (pinfunction "VDD_2_16") (pintype "power_in"))
      (node (ref "U3") (pin "32") (pinfunction "VDD_3_32") (pintype "power_in"))
      (node (ref "U3") (pin "48") (pinfunction "VDD_4_48") (pintype "power_in"))
      (node (ref "U3") (pin "64") (pinfunction "VDD_64") (pintype "power_in"))
      (node (ref "U4") (pin "1") (pinfunction "IN_1") (pintype "input"))
      (node (ref "U5") (pin "1") (pinfunction "IN_1") (pintype "input"))
      (node (ref "U6") (pin "12") (pinfunction "VCC_12") (pintype "power_in"))
      (node (ref "U7") (pin "5") (pinfunction "VS_5") (pintype "power_in"))
      (node (ref "U8") (pin "8") (pinfunction "VCC_8") (pintype "passive"))
      (node (ref "U9") (pin "6") (pinfunction "VDD_6") (pintype "power_in"))
      (node (ref "U9") (pin "7") (pinfunction "VREGIN_7") (pintype "input"))
    )
    (net (code "4") (name "+5V") (class "Default")
      (node (ref "C2") (pin "1") (pinfunction "1_1") (pintype "passive"))
      (node (ref "C29") (pin "1") (pinfunction "1_1") (pintype "passive"))
      (node (ref "C3") (pin "2") (pinfunction "2_2") (pintype "passive"))
      (node (ref "R1") (pin "2") (pinfunction "2_2") (pintype "passive"))
      (node (ref "R2") (pin "2") (pinfunction "2_2") (pintype "passive"))
      (node (ref "R23") (pin "1") (pinfunction "1_1") (pintype "passive"))
      (node (ref "TP1") (pin "1") (pinfunction "P$1_1") (pintype "bidirectional"))
      (node (ref "U1") (pin "2") (pinfunction "VOUT_2") (pintype "power_in"))
      (node (ref "U11") (pin "3") (pinfunction "VCC_3") (pintype "power_in"))
      (node (ref "U2") (pin "1") (pinfunction "IN_1") (pintype "input"))
      (node (ref "U2") (pin "3") (pinfunction "EN_3") (pintype "input"))
    )
    (net (code "5") (name "ACS_ADC") (class "Default")
      (node (ref "TP5") (pin "1") (pinfunction "P$1_1") (pintype "bidirectional"))
      (node (ref "U3") (pin "12") (pinfunction "PA0_12") (pintype "bidirectional"))
      (node (ref "U6") (pin "11") (pinfunction "VIOUT_11") (pintype "output"))
    )
    (net (code "6") (name "BMS_NFAULT") (class "Default")
      (node (ref "J4") (pin "5") (pinfunction "5_5") (pintype "passive"))
      (node (ref "JP1") (pin "4") (pinfunction "4_4") (pintype "passive"))
      (node (ref "U3") (pin "19") (pinfunction "PA5_19") (pintype "bidirectional"))
    )
    (net (code "7") (name "BMS_WAKEUP") (class "Default")
      (node (ref "J4") (pin "4") (pinfunction "4_4") (pintype "passive"))
      (node (ref "JP1") (pin "3") (pinfunction "3_3") (pintype "passive"))
      (node (ref "U3") (pin "18") (pinfunction "PA4_18") (pintype "bidirectional"))
    )
    (net (code "8") (name "BUTTON1") (class "Default")
      (node (ref "C20") (pin "1") (pinfunction "1_1") (pintype "passive"))
      (node (ref "R10") (pin "1") (pinfunction "1_1") (pintype "passive"))
      (node (ref "S2") (pin "1") (pinfunction "1_1") (pintype "passive"))
      (node (ref "S2") (pin "2") (pinfunction "2_2") (pintype "passive"))
      (node (ref "U3") (pin "2") (pinfunction "PC13_2") (pintype "bidirectional"))
    )
    (net (code "9") (name "BUTTON2") (class "Default")
      (node (ref "C21") (pin "1") (pinfunction "1_1") (pintype "passive"))
      (node (ref "R11") (pin "1") (pinfunction "1_1") (pintype "passive"))
      (node (ref "S3") (pin "1") (pinfunction "1_1") (pintype "passive"))
      (node (ref "S3") (pin "2") (pinfunction "2_2") (pintype "passive"))
      (node (ref "U3") (pin "3") (pinfunction "PC14-OSC32_IN_3") (pintype "bidirectional"))
    )
    (net (code "10") (name "BUTTON3") (class "Default")
      (node (ref "C22") (pin "1") (pinfunction "1_1") (pintype "passive"))
      (node (ref "R12") (pin "1") (pinfunction "1_1") (pintype "passive"))
      (node (ref "S4") (pin "1") (pinfunction "1_1") (pintype "passive"))
      (node (ref "S4") (pin "2") (pinfunction "2_2") (pintype "passive"))
      (node (ref "U3") (pin "4") (pinfunction "PC15-OSC32_OUT_4") (pintype "bidirectional"))
    )
    (net (code "11") (name "CAN_RX") (class "Default")
      (node (ref "TP8") (pin "1") (pinfunction "P$1_1") (pintype "bidirectional"))
      (node (ref "U11") (pin "4") (pinfunction "RXD_4") (pintype "output"))
      (node (ref "U3") (pin "61") (pinfunction "PB8-BOOT0_61") (pintype "bidirectional"))
    )
    (net (code "12") (name "CAN_STB") (class "Default")
      (node (ref "U11") (pin "8") (pinfunction "STB_8") (pintype "input"))
      (node (ref "U3") (pin "60") (pinfunction "PB7_60") (pintype "bidirectional"))
    )
    (net (code "13") (name "CAN_TX") (class "Default")
      (node (ref "TP7") (pin "1") (pinfunction "P$1_1") (pintype "bidirectional"))
      (node (ref "U11") (pin "1") (pinfunction "TXD_1") (pintype "input"))
      (node (ref "U3") (pin "62") (pinfunction "PB9_62") (pintype "bidirectional"))
    )
    (net (code "14") (name "CP_WAKEUP") (class "Default")
      (node (ref "SB1") (pin "1") (pinfunction "1_1") (pintype "passive"))
      (node (ref "U9") (pin "13") (pinfunction "WAKEUP_13") (pintype "input"))
    )
    (net (code "15") (name "DRV_IN1") (class "Default")
      (node (ref "U12") (pin "15") (pinfunction "PH_IN1_15") (pintype "input"))
      (node (ref "U3") (pin "40") (pinfunction "PC8_40") (pintype "bidirectional"))
    )
    (net (code "16") (name "DRV_IN2") (class "Default")
      (node (ref "U12") (pin "14") (pinfunction "EN_IN2_14") (pintype "input"))
      (node (ref "U3") (pin "41") (pinfunction "PC9_41") (pintype "bidirectional"))
    )
    (net (code "17") (name "DRV_NFAULT") (class "Default")
      (node (ref "R26") (pin "1") (pinfunction "1_1") (pintype "passive"))
      (node (ref "U12") (pin "9") (pinfunction "FAULT_N_9") (pintype "open_collector"))
      (node (ref "U3") (pin "35") (pinfunction "PB13_35") (pintype "bidirectional"))
    )
    (net (code "18") (name "DRV_NSLEEP") (class "Default")
      (node (ref "U12") (pin "13") (pinfunction "SLEEP_N_13") (pintype "input"))
      (node (ref "U3") (pin "37") (pinfunction "PB15_37") (pintype "bidirectional"))
    )
    (net (code "19") (name "DRV_SNSOUT") (class "Default")
      (node (ref "R27") (pin "1") (pinfunction "1_1") (pintype "passive"))
      (node (ref "U12") (pin "10") (pinfunction "SNSOUT_10") (pintype "open_collector"))
      (node (ref "U3") (pin "36") (pinfunction "PB14_36") (pintype "bidirectional"))
    )
    (net (code "20") (name "DRV_SO") (class "Default")
      (node (ref "SB3") (pin "1") (pinfunction "1_1") (pintype "passive"))
      (node (ref "U3") (pin "26") (pinfunction "PB2_26") (pintype "bidirectional"))
    )
    (net (code "21") (name "GH1") (class "Default")
      (node (ref "Q1") (pin "4") (pinfunction "G_4") (pintype "passive"))
      (node (ref "U12") (pin "17") (pinfunction "GH1_17") (pintype "power_in"))
    )
    (net (code "22") (name "GH2") (class "Default")
      (node (ref "Q4") (pin "4") (pinfunction "G_4") (pintype "passive"))
      (node (ref "U12") (pin "24") (pinfunction "GH2_24") (pintype "power_in"))
    )
    (net (code "23") (name "GL1") (class "Default")
      (node (ref "Q2") (pin "4") (pinfunction "G_4") (pintype "passive"))
      (node (ref "U12") (pin "19") (pinfunction "GL1_19") (pintype "output"))
    )
    (net (code "24") (name "GL2") (class "Default")
      (node (ref "Q3") (pin "4") (pinfunction "G_4") (pintype "passive"))
      (node (ref "U12") (pin "22") (pinfunction "GL2_22") (pintype "output"))
    )
    (net (code "25") (name "GND") (class "Default")
      (node (ref "C1") (pin "2") (pinfunction "2_2") (pintype "passive"))
      (node (ref "C10") (pin "1") (pinfunction "1_1") (pintype "passive"))
      (node (ref "C11") (pin "2") (pinfunction "2_2") (pintype "passive"))
      (node (ref "C12") (pin "2") (pinfunction "2_2") (pintype "passive"))
      (node (ref "C13") (pin "1") (pinfunction "1_1") (pintype "passive"))
      (node (ref "C14") (pin "2") (pinfunction "2_2") (pintype "passive"))
      (node (ref "C15") (pin "2") (pinfunction "2_2") (pintype "passive"))
      (node (ref "C16") (pin "2") (pinfunction "2_2") (pintype "passive"))
      (node (ref "C17") (pin "2") (pinfunction "2_2") (pintype "passive"))
      (node (ref "C18") (pin "2") (pinfunction "2_2") (pintype "passive"))
      (node (ref "C19") (pin "2") (pinfunction "2_2") (pintype "passive"))
      (node (ref "C2") (pin "2") (pinfunction "2_2") (pintype "passive"))
      (node (ref "C20") (pin "2") (pinfunction "2_2") (pintype "passive"))
      (node (ref "C21") (pin "2") (pinfunction "2_2") (pintype "passive"))
      (node (ref "C22") (pin "2") (pinfunction "2_2") (pintype "passive"))
      (node (ref "C23") (pin "2") (pinfunction "2_2") (pintype "passive"))
      (node (ref "C24") (pin "1") (pinfunction "1_1") (pintype "passive"))
      (node (ref "C25") (pin "1") (pinfunction "1_1") (pintype "passive"))
      (node (ref "C26") (pin "2") (pinfunction "2_2") (pintype "passive"))
      (node (ref "C27") (pin "2") (pinfunction "2_2") (pintype "passive"))
      (node (ref "C28") (pin "2") (pinfunction "2_2") (pintype "passive"))
      (node (ref "C29") (pin "2") (pinfunction "2_2") (pintype "passive"))
      (node (ref "C3") (pin "1") (pinfunction "1_1") (pintype "passive"))
      (node (ref "C30") (pin "2") (pinfunction "2_2") (pintype "passive"))
      (node (ref "C31") (pin "2") (pinfunction "2_2") (pintype "passive"))
      (node (ref "C32") (pin "2") (pinfunction "2_2") (pintype "passive"))
      (node (ref "C35") (pin "1") (pinfunction "1_1") (pintype "passive"))
      (node (ref "C36") (pin "1") (pinfunction "1_1") (pintype "passive"))
      (node (ref "C37") (pin "2") (pinfunction "-_2") (pintype "passive"))
      (node (ref "C38") (pin "2") (pinfunction "2_2") (pintype "passive"))
      (node (ref "C39") (pin "2") (pinfunction "-_2") (pintype "passive"))
      (node (ref "C4") (pin "2") (pinfunction "2_2") (pintype "passive"))
      (node (ref "C40") (pin "2") (pinfunction "2_2") (pintype "passive"))
      (node (ref "C5") (pin "1") (pinfunction "1_1") (pintype "passive"))
      (node (ref "C6") (pin "1") (pinfunction "1_1") (pintype "passive"))
      (node (ref "C7") (pin "1") (pinfunction "1_1") (pintype "passive"))
      (node (ref "C8") (pin "1") (pinfunction "1_1") (pintype "passive"))
      (node (ref "C9") (pin "1") (pinfunction "1_1") (pintype "passive"))
      (node (ref "D1") (pin "-") (pinfunction "C_-") (pintype "passive"))
      (node (ref "D2") (pin "-") (pinfunction "C_-") (pintype "passive"))
      (node (ref "D3") (pin "-") (pinfunction "C_-") (pintype "passive"))
      (node (ref "D4") (pin "-") (pinfunction "C_-") (pintype "passive"))
      (node (ref "D5") (pin "-") (pinfunction "C_-") (pintype "passive"))
      (node (ref "D6") (pin "1") (pinfunction "1_1") (pintype "passive"))
      (node (ref "D7") (pin "3") (pinfunction "3_3") (pintype "passive"))
      (node (ref "D8") (pin "1") (pinfunction "1_1") (pintype "passive"))
      (node (ref "J1") (pin "1") (pinfunction "1_1") (pintype "passive"))
      (node (ref "J14") (pin "GND1") (pinfunction "GND_GND1") (pintype "bidirectional"))
      (node (ref "J2") (pin "4") (pinfunction "4_4") (pintype "passive"))
      (node (ref "J3") (pin "4") (pinfunction "4_4") (pintype "passive"))
      (node (ref "J4") (pin "6") (pinfunction "6_6") (pintype "passive"))
      (node (ref "J5") (pin "6") (pinfunction "6_6") (pintype "passive"))
      (node (ref "J8") (pin "4") (pinfunction "4_4") (pintype "passive"))
      (node (ref "J9") (pin "GND1") (pinfunction "GND_GND1") (pintype "bidirectional"))
      (node (ref "R20") (pin "1") (pinfunction "1_1") (pintype "passive"))
      (node (ref "R25") (pin "1") (pinfunction "1_1") (pintype "passive"))
      (node (ref "R28") (pin "1") (pinfunction "1_1") (pintype "passive"))
      (node (ref "R29") (pin "1") (pinfunction "1_1") (pintype "passive"))
      (node (ref "R3") (pin "1") (pinfunction "1_1") (pintype "passive"))
      (node (ref "R7") (pin "P$3") (pinfunction "3_P$3") (pintype "passive"))
      (node (ref "R8") (pin "P$3") (pinfunction "3_P$3") (pintype "passive"))
      (node (ref "R9") (pin "P$3") (pinfunction "3_P$3") (pintype "passive"))
      (node (ref "S1") (pin "3") (pinfunction "3_3") (pintype "passive"))
      (node (ref "S1") (pin "4") (pinfunction "4_4") (pintype "passive"))
      (node (ref "S2") (pin "3") (pinfunction "3_3") (pintype "passive"))
      (node (ref "S2") (pin "4") (pinfunction "4_4") (pintype "passive"))
      (node (ref "S3") (pin "3") (pinfunction "3_3") (pintype "passive"))
      (node (ref "S3") (pin "4") (pinfunction "4_4") (pintype "passive"))
      (node (ref "S4") (pin "3") (pinfunction "3_3") (pintype "passive"))
      (node (ref "S4") (pin "4") (pinfunction "4_4") (pintype "passive"))
      (node (ref "TP11") (pin "1") (pinfunction "P$1_1") (pintype "bidirectional"))
      (node (ref "U1") (pin "4") (pinfunction "GND_2_4") (pintype "power_in"))
      (node (ref "U1") (pin "5") (pinfunction "GND_5") (pintype "power_in"))
      (node (ref "U1") (pin "9") (pinfunction "PAD_9") (pintype "power_in"))
      (node (ref "U10") (pin "5") (pinfunction "GND_5") (pintype "power_in"))
      (node (ref "U11") (pin "2") (pinfunction "GND_2") (pintype "power_in"))
      (node (ref "U12") (pin "16") (pinfunction "GND_2_16") (pintype "power_in"))
      (node (ref "U12") (pin "20") (pinfunction "SN_20") (pintype "input"))
      (node (ref "U12") (pin "25") (pinfunction "PAD_25") (pintype "power_in"))
      (node (ref "U12") (pin "5") (pinfunction "GND_5") (pintype "power_in"))
      (node (ref "U2") (pin "2") (pinfunction "GND_2") (pintype "power_in"))
      (node (ref "U3") (pin "15") (pinfunction "VSS_2_15") (pintype "power_in"))
      (node (ref "U3") (pin "27") (pinfunction "VSSA_27") (pintype "power_in"))
      (node (ref "U3") (pin "31") (pinfunction "VSS_3_31") (pintype "power_in"))
      (node (ref "U3") (pin "47") (pinfunction "VSS_4_47") (pintype "power_in"))
      (node (ref "U3") (pin "63") (pinfunction "VSS_63") (pintype "power_in"))
      (node (ref "U4") (pin "3") (pinfunction "GND_3") (pintype "power_in"))
      (node (ref "U5") (pin "3") (pinfunction "GND_3") (pintype "power_in"))
      (node (ref "U6") (pin "5") (pinfunction "GND_5") (pintype "power_in"))
      (node (ref "U7") (pin "1") (pinfunction "NC_1") (pintype "output"))
      (node (ref "U7") (pin "4") (pinfunction "GND_4") (pintype "power_in"))
      (node (ref "U8") (pin "1") (pinfunction "A_0_1") (pintype "passive"))
      (node (ref "U8") (pin "2") (pinfunction "A_1_2") (pintype "passive"))
      (node (ref "U8") (pin "3") (pinfunction "A_2_3") (pintype "passive"))
      (node (ref "U8") (pin "4") (pinfunction "VSS_4") (pintype "passive"))
      (node (ref "U8") (pin "7") (pinfunction "WP_7") (pintype "passive"))
      (node (ref "U9") (pin "12") (pinfunction "GND_3_12") (pintype "power_in"))
      (node (ref "U9") (pin "15") (pinfunction "CTS_15") (pintype "input"))
      (node (ref "U9") (pin "21") (pinfunction "GND_21") (pintype "power_in"))
      (node (ref "U9") (pin "3") (pinfunction "GND_2_3") (pintype "power_in"))
      (node (ref "X1") (pin "2") (pinfunction "GND_2") (pintype "passive"))
    )
    (net (code "26") (name "I2C2_SCL") (class "Default")
      (node (ref "J8") (pin "2") (pinfunction "2_2") (pintype "passive"))
      (node (ref "R15") (pin "1") (pinfunction "1_1") (pintype "passive"))
      (node (ref "U3") (pin "43") (pinfunction "PA9_43") (pintype "bidirectional"))
      (node (ref "U8") (pin "6") (pinfunction "SERIAL_CLK_6") (pintype "passive"))
    )
    (net (code "27") (name "I2C2_SDA") (class "Default")
      (node (ref "J8") (pin "3") (pinfunction "3_3") (pintype "passive"))
      (node (ref "R16") (pin "1") (pinfunction "1_1") (pintype "passive"))
      (node (ref "U3") (pin "42") (pinfunction "PA8_42") (pintype "bidirectional"))
      (node (ref "U8") (pin "5") (pinfunction "SER_DATA_I/O_5") (pintype "passive"))
    )
    (net (code "28") (name "INA_ADC") (class "Default")
      (node (ref "TP6") (pin "1") (pinfunction "P$1_1") (pintype "bidirectional"))
      (node (ref "U3") (pin "13") (pinfunction "PA1_13") (pintype "bidirectional"))
      (node (ref "U7") (pin "8") (pinfunction "OUT_8") (pintype "output"))
    )
    (net (code "29") (name "LED1") (class "Default")
      (node (ref "RM1") (pin "1") (pinfunction "1_1") (pintype "passive"))
      (node (ref "U3") (pin "59") (pinfunction "PB6_59") (pintype "bidirectional"))
    )
    (net (code "30") (name "LED2") (class "Default")
      (node (ref "RM1") (pin "2") (pinfunction "1_2") (pintype "passive"))
      (node (ref "U3") (pin "58") (pinfunction "PB5_58") (pintype "bidirectional"))
    )
    (net (code "31") (name "LED3") (class "Default")
      (node (ref "RM1") (pin "3") (pinfunction "1_3") (pintype "passive"))
      (node (ref "U3") (pin "57") (pinfunction "PB4_57") (pintype "bidirectional"))
    )
    (net (code "32") (name "LED4") (class "Default")
      (node (ref "RM1") (pin "4") (pinfunction "1_4") (pintype "passive"))
      (node (ref "U3") (pin "56") (pinfunction "PB3_56") (pintype "bidirectional"))
    )
    (net (code "33") (name "MOTOR_ENCODER1") (class "Default")
      (node (ref "J3") (pin "2") (pinfunction "2_2") (pintype "passive"))
      (node (ref "U3") (pin "38") (pinfunction "PC6_38") (pintype "bidirectional"))
    )
    (net (code "34") (name "MOTOR_ENCODER2") (class "Default")
      (node (ref "J3") (pin "3") (pinfunction "3_3") (pintype "passive"))
      (node (ref "U3") (pin "39") (pinfunction "PC7_39") (pintype "bidirectional"))
    )
    (net (code "35") (name "Net-(D1-A)") (class "Default")
      (node (ref "D1") (pin "+") (pinfunction "A_+") (pintype "passive"))
      (node (ref "RM1") (pin "8") (pinfunction "2_8") (pintype "passive"))
    )
    (net (code "36") (name "Net-(D2-A)") (class "Default")
      (node (ref "D2") (pin "+") (pinfunction "A_+") (pintype "passive"))
      (node (ref "RM1") (pin "7") (pinfunction "2_7") (pintype "passive"))
    )
    (net (code "37") (name "Net-(D3-A)") (class "Default")
      (node (ref "D3") (pin "+") (pinfunction "A_+") (pintype "passive"))
      (node (ref "RM1") (pin "6") (pinfunction "2_6") (pintype "passive"))
    )
    (net (code "38") (name "Net-(D4-A)") (class "Default")
      (node (ref "D4") (pin "+") (pinfunction "A_+") (pintype "passive"))
      (node (ref "RM1") (pin "5") (pinfunction "2_5") (pintype "passive"))
    )
    (net (code "39") (name "Net-(D5-A)") (class "Default")
      (node (ref "D5") (pin "+") (pinfunction "A_+") (pintype "passive"))
      (node (ref "R17") (pin "1") (pinfunction "1_1") (pintype "passive"))
    )
    (net (code "40") (name "Net-(J9-D+)") (class "Default")
      (node (ref "D6") (pin "3") (pinfunction "3_3") (pintype "passive"))
      (node (ref "J9") (pin "D+1") (pinfunction "D+_D+1") (pintype "bidirectional"))
      (node (ref "U9") (pin "4") (pinfunction "D+_4") (pintype "passive"))
    )
    (net (code "41") (name "Net-(J9-D-)") (class "Default")
      (node (ref "D6") (pin "4") (pinfunction "4_4") (pintype "passive"))
      (node (ref "J9") (pin "D-1") (pinfunction "D-_D-1") (pintype "bidirectional"))
      (node (ref "U9") (pin "5") (pinfunction "D-_5") (pintype "passive"))
    )
    (net (code "42") (name "Net-(J9-VBUS)") (class "Default")
      (node (ref "C27") (pin "1") (pinfunction "1_1") (pintype "passive"))
      (node (ref "D6") (pin "2") (pinfunction "2_2") (pintype "passive"))
      (node (ref "J9") (pin "VBUS1") (pinfunction "VBUS_VBUS1") (pintype "bidirectional"))
      (node (ref "U9") (pin "8") (pinfunction "VBUS_8") (pintype "input"))
    )
    (net (code "43") (name "Net-(J14-VBUS)") (class "Default")
      (node (ref "D8") (pin "2") (pinfunction "2_2") (pintype "passive"))
      (node (ref "J14") (pin "VBUS1") (pinfunction "VBUS_VBUS1") (pintype "bidirectional"))
      (node (ref "R23") (pin "2") (pinfunction "2_2") (pintype "passive"))
    )
    (net (code "44") (name "Net-(TP9-P$1)") (class "Default")
      (node (ref "SB3") (pin "2") (pinfunction "2_2") (pintype "passive"))
      (node (ref "TP9") (pin "1") (pinfunction "P$1_1") (pintype "bidirectional"))
      (node (ref "U12") (pin "11") (pinfunction "SO_11") (pintype "output"))
    )
    (net (code "45") (name "Net-(U1-DELAY)") (class "Default")
      (node (ref "R1") (pin "1") (pinfunction "1_1") (pintype "passive"))
      (node (ref "U1") (pin "1") (pinfunction "DELAY_1") (pintype "input"))
    )
    (net (code "46") (name "Net-(U1-FB)") (class "Default")
      (node (ref "R2") (pin "1") (pinfunction "1_1") (pintype "passive"))
      (node (ref "R3") (pin "2") (pinfunction "2_2") (pintype "passive"))
      (node (ref "U1") (pin "3") (pinfunction "FB_3") (pintype "input"))
    )
    (net (code "47") (name "Net-(U2-BYP)") (class "Default")
      (node (ref "C4") (pin "1") (pinfunction "1_1") (pintype "passive"))
      (node (ref "U2") (pin "4") (pinfunction "BYP_4") (pintype "passive"))
    )
    (net (code "48") (name "Net-(U3A-PA11)") (class "Default")
      (node (ref "R4") (pin "2") (pinfunction "2_2") (pintype "passive"))
      (node (ref "U3") (pin "45") (pinfunction "PA11_45") (pintype "bidirectional"))
    )
    (net (code "49") (name "Net-(U3A-PA12)") (class "Default")
      (node (ref "R5") (pin "2") (pinfunction "2_2") (pintype "passive"))
      (node (ref "U3") (pin "46") (pinfunction "PA12_46") (pintype "bidirectional"))
    )
    (net (code "50") (name "Net-(U3A-PB12)") (class "Default")
      (node (ref "SB1") (pin "2") (pinfunction "2_2") (pintype "passive"))
      (node (ref "U3") (pin "34") (pinfunction "PB12_34") (pintype "bidirectional"))
    )
    (net (code "51") (name "Net-(U3A-PF0-OSC_IN)") (class "Default")
      (node (ref "U3") (pin "5") (pinfunction "PF0-OSC_IN_5") (pintype "bidirectional"))
      (node (ref "X1") (pin "3") (pinfunction "OUT_3") (pintype "passive"))
    )
    (net (code "52") (name "Net-(U3A-PF1-OSC_OUT)") (class "Default")
      (node (ref "U3") (pin "6") (pinfunction "PF1-OSC_OUT_6") (pintype "bidirectional"))
      (node (ref "X1") (pin "1") (pinfunction "IN_1") (pintype "passive"))
    )
    (net (code "53") (name "Net-(U3A-PG10-NRST)") (class "Default")
      (node (ref "C19") (pin "1") (pinfunction "1_1") (pintype "passive"))
      (node (ref "R6") (pin "1") (pinfunction "1_1") (pintype "passive"))
      (node (ref "S1") (pin "1") (pinfunction "1_1") (pintype "passive"))
      (node (ref "S1") (pin "2") (pinfunction "2_2") (pintype "passive"))
      (node (ref "U3") (pin "7") (pinfunction "PG10-NRST_7") (pintype "bidirectional"))
    )
    (net (code "54") (name "Net-(U3B-VDDA)") (class "Default")
      (node (ref "C10") (pin "2") (pinfunction "2_2") (pintype "passive"))
      (node (ref "C11") (pin "1") (pinfunction "1_1") (pintype "passive"))
      (node (ref "L1") (pin "1") (pinfunction "1_1") (pintype "passive"))
      (node (ref "SB2") (pin "1") (pinfunction "1_1") (pintype "passive"))
      (node (ref "U3") (pin "29") (pinfunction "VDDA_29") (pintype "power_in"))
    )
    (net (code "55") (name "Net-(U6-IP+)") (class "Default")
      (node (ref "J6") (pin "1") (pinfunction "1_1") (pintype "passive"))
      (node (ref "U6") (pin "1") (pinfunction "IP+_1") (pintype "input"))
    )
    (net (code "56") (name "Net-(U6-IP–)") (class "Default")
      (node (ref "J6") (pin "2") (pinfunction "2_2") (pintype "passive"))
      (node (ref "U6") (pin "3") (pinfunction "IP–_3") (pintype "input"))
    )
    (net (code "57") (name "Net-(U6-~{FAULT})") (class "Default")
      (node (ref "R13") (pin "1") (pinfunction "1_1") (pintype "passive"))
      (node (ref "U6") (pin "6") (pinfunction "~{FAULT}_6") (pintype "input"))
    )
    (net (code "58") (name "Net-(U7-IN+)") (class "Default")
      (node (ref "J7") (pin "1") (pinfunction "1_1") (pintype "passive"))
      (node (ref "R14") (pin "2") (pinfunction "2_2") (pintype "passive"))
      (node (ref "U7") (pin "2") (pinfunction "IN+_2") (pintype "input"))
    )
    (net (code "59") (name "Net-(U7-IN-)") (class "Default")
      (node (ref "J7") (pin "2") (pinfunction "2_2") (pintype "passive"))
      (node (ref "R14") (pin "1") (pinfunction "1_1") (pintype "passive"))
      (node (ref "U7") (pin "3") (pinfunction "IN-_3") (pintype "input"))
    )
    (net (code "60") (name "Net-(U9-RSTB)") (class "Default")
      (node (ref "R18") (pin "1") (pinfunction "1_1") (pintype "passive"))
      (node (ref "U9") (pin "9") (pinfunction "RSTB_9") (pintype "input"))
    )
    (net (code "61") (name "Net-(U9-SUSPENDB)") (class "Default")
      (node (ref "R17") (pin "2") (pinfunction "2_2") (pintype "passive"))
      (node (ref "U9") (pin "11") (pinfunction "SUSPENDB_11") (pintype "output"))
    )
    (net (code "62") (name "Net-(U10-A)") (class "Default")
      (node (ref "D7") (pin "1") (pinfunction "1_1") (pintype "passive"))
      (node (ref "J10") (pin "1") (pinfunction "1_1") (pintype "passive"))
      (node (ref "J11") (pin "1") (pinfunction "1_1") (pintype "passive"))
      (node (ref "R21") (pin "1") (pinfunction "1_1") (pintype "passive"))
      (node (ref "U10") (pin "6") (pinfunction "A_6") (pintype "bidirectional"))
    )
    (net (code "63") (name "Net-(U10-B)") (class "Default")
      (node (ref "D7") (pin "2") (pinfunction "2_2") (pintype "passive"))
      (node (ref "J10") (pin "2") (pinfunction "2_2") (pintype "passive"))
      (node (ref "J11") (pin "2") (pinfunction "2_2") (pintype "passive"))
      (node (ref "R21") (pin "2") (pinfunction "2_2") (pintype "passive"))
      (node (ref "U10") (pin "7") (pinfunction "B_7") (pintype "bidirectional"))
    )
    (net (code "64") (name "Net-(U11-CANH)") (class "Default")
      (node (ref "J12") (pin "2") (pinfunction "2_2") (pintype "passive"))
      (node (ref "J13") (pin "2") (pinfunction "2_2") (pintype "passive"))
      (node (ref "R22") (pin "1") (pinfunction "1_1") (pintype "passive"))
      (node (ref "U11") (pin "7") (pinfunction "CANH_7") (pintype "bidirectional"))
    )
    (net (code "65") (name "Net-(U11-CANL)") (class "Default")
      (node (ref "J12") (pin "1") (pinfunction "1_1") (pintype "passive"))
      (node (ref "J13") (pin "1") (pinfunction "1_1") (pintype "passive"))
      (node (ref "R22") (pin "2") (pinfunction "2_2") (pintype "passive"))
      (node (ref "U11") (pin "6") (pinfunction "CANL_6") (pintype "bidirectional"))
    )
    (net (code "66") (name "Net-(U12-AVDD)") (class "Default")
      (node (ref "C35") (pin "2") (pinfunction "2_2") (pintype "passive"))
      (node (ref "R24") (pin "2") (pinfunction "2_2") (pintype "passive"))
      (node (ref "U12") (pin "7") (pinfunction "AVDD_7") (pintype "power_in"))
    )
    (net (code "67") (name "Net-(U12-CPH)") (class "Default")
      (node (ref "C33") (pin "1") (pinfunction "1_1") (pintype "passive"))
      (node (ref "U12") (pin "3") (pinfunction "CPH_3") (pintype "passive"))
    )
    (net (code "68") (name "Net-(U12-CPL)") (class "Default")
      (node (ref "C33") (pin "2") (pinfunction "2_2") (pintype "passive"))
      (node (ref "U12") (pin "4") (pinfunction "CPL_4") (pintype "passive"))
    )
    (net (code "69") (name "Net-(U12-DVDD)") (class "Default")
      (node (ref "C36") (pin "2") (pinfunction "2_2") (pintype "passive"))
      (node (ref "R26") (pin "2") (pinfunction "2_2") (pintype "passive"))
      (node (ref "R27") (pin "2") (pinfunction "2_2") (pintype "passive"))
      (node (ref "U12") (pin "8") (pinfunction "DVDD_8") (pintype "power_in"))
    )
    (net (code "70") (name "Net-(U12-IDRIVE)") (class "Default")
      (node (ref "R28") (pin "2") (pinfunction "2_2") (pintype "passive"))
      (node (ref "U12") (pin "12") (pinfunction "IDRIVE_12") (pintype "input"))
    )
    (net (code "71") (name "Net-(U12-VCP)") (class "Default")
      (node (ref "C34") (pin "2") (pinfunction "2_2") (pintype "passive"))
      (node (ref "U12") (pin "2") (pinfunction "VCP_2") (pintype "power_in"))
    )
    (net (code "72") (name "Net-(U12-VREF)") (class "Default")
      (node (ref "R24") (pin "1") (pinfunction "1_1") (pintype "passive"))
      (node (ref "R25") (pin "2") (pinfunction "2_2") (pintype "passive"))
      (node (ref "U12") (pin "6") (pinfunction "VREF_6") (pintype "input"))
    )
    (net (code "73") (name "POT_1") (class "Default")
      (node (ref "R7") (pin "P$2") (pinfunction "2_P$2") (pintype "passive"))
      (node (ref "U3") (pin "9") (pinfunction "PC1_9") (pintype "bidirectional"))
    )
    (net (code "74") (name "POT_2") (class "Default")
      (node (ref "R8") (pin "P$2") (pinfunction "2_P$2") (pintype "passive"))
      (node (ref "U3") (pin "10") (pinfunction "PC2_10") (pintype "bidirectional"))
    )
    (net (code "75") (name "POT_3") (class "Default")
      (node (ref "R9") (pin "P$2") (pinfunction "2_P$2") (pintype "passive"))
      (node (ref "U3") (pin "11") (pinfunction "PC3_11") (pintype "bidirectional"))
    )
    (net (code "76") (name "RS_485_RD") (class "Default")
      (node (ref "R20") (pin "2") (pinfunction "2_2") (pintype "passive"))
      (node (ref "U10") (pin "2") (pinfunction "~{RE}_2") (pintype "input"))
      (node (ref "U10") (pin "3") (pinfunction "DE_3") (pintype "input"))
      (node (ref "U3") (pin "24") (pinfunction "PB0_24") (pintype "bidirectional"))
    )
    (net (code "77") (name "SH1") (class "Default")
      (node (ref "J15") (pin "1") (pinfunction "1_1") (pintype "passive"))
      (node (ref "Q1") (pin "1") (pinfunction "S_1") (pintype "passive"))
      (node (ref "Q1") (pin "2") (pinfunction "S_2") (pintype "passive"))
      (node (ref "Q1") (pin "3") (pinfunction "S_3") (pintype "passive"))
      (node (ref "Q2") (pin "5") (pinfunction "D_5") (pintype "passive"))
      (node (ref "Q2") (pin "6") (pinfunction "D_6") (pintype "passive"))
      (node (ref "Q2") (pin "7") (pinfunction "D_7") (pintype "passive"))
      (node (ref "Q2") (pin "8") (pinfunction "D_8") (pintype "passive"))
      (node (ref "Q2") (pin "9") (pinfunction "D_9") (pintype "passive"))
      (node (ref "U12") (pin "18") (pinfunction "SH1_18") (pintype "input"))
    )
    (net (code "78") (name "SH2") (class "Default")
      (node (ref "J15") (pin "2") (pinfunction "2_2") (pintype "passive"))
      (node (ref "Q3") (pin "5") (pinfunction "D_5") (pintype "passive"))
      (node (ref "Q3") (pin "6") (pinfunction "D_6") (pintype "passive"))
      (node (ref "Q3") (pin "7") (pinfunction "D_7") (pintype "passive"))
      (node (ref "Q3") (pin "8") (pinfunction "D_8") (pintype "passive"))
      (node (ref "Q3") (pin "9") (pinfunction "D_9") (pintype "passive"))
      (node (ref "Q4") (pin "1") (pinfunction "S_1") (pintype "passive"))
      (node (ref "Q4") (pin "2") (pinfunction "S_2") (pintype "passive"))
      (node (ref "Q4") (pin "3") (pinfunction "S_3") (pintype "passive"))
      (node (ref "U12") (pin "23") (pinfunction "SH2_23") (pintype "input"))
    )
    (net (code "79") (name "SP") (class "Default")
      (node (ref "Q2") (pin "1") (pinfunction "S_1") (pintype "passive"))
      (node (ref "Q2") (pin "2") (pinfunction "S_2") (pintype "passive"))
      (node (ref "Q2") (pin "3") (pinfunction "S_3") (pintype "passive"))
      (node (ref "Q3") (pin "1") (pinfunction "S_1") (pintype "passive"))
      (node (ref "Q3") (pin "2") (pinfunction "S_2") (pintype "passive"))
      (node (ref "Q3") (pin "3") (pinfunction "S_3") (pintype "passive"))
      (node (ref "R29") (pin "2") (pinfunction "2_2") (pintype "passive"))
      (node (ref "TP12") (pin "1") (pinfunction "P$1_1") (pintype "bidirectional"))
      (node (ref "U12") (pin "21") (pinfunction "SP_21") (pintype "input"))
    )
    (net (code "80") (name "SPI3_MISO") (class "Default")
      (node (ref "J5") (pin "3") (pinfunction "3_3") (pintype "passive"))
      (node (ref "U3") (pin "53") (pinfunction "PC11_53") (pintype "bidirectional"))
    )
    (net (code "81") (name "SPI3_MOSI") (class "Default")
      (node (ref "J5") (pin "4") (pinfunction "4_4") (pintype "passive"))
      (node (ref "U3") (pin "54") (pinfunction "PC12_54") (pintype "bidirectional"))
    )
    (net (code "82") (name "SPI3_SCK") (class "Default")
      (node (ref "J5") (pin "2") (pinfunction "2_2") (pintype "passive"))
      (node (ref "U3") (pin "52") (pinfunction "PC10_52") (pintype "bidirectional"))
    )
    (net (code "83") (name "SPI3_USER_CS") (class "Default")
      (node (ref "J5") (pin "5") (pinfunction "5_5") (pintype "passive"))
      (node (ref "U3") (pin "55") (pinfunction "PD2_55") (pintype "bidirectional"))
    )
    (net (code "84") (name "SWCLK") (class "Default")
      (node (ref "J2") (pin "3") (pinfunction "3_3") (pintype "passive"))
      (node (ref "U3") (pin "50") (pinfunction "PA14_50") (pintype "bidirectional"))
    )
    (net (code "85") (name "SWDIO") (class "Default")
      (node (ref "J2") (pin "2") (pinfunction "2_2") (pintype "passive"))
      (node (ref "U3") (pin "49") (pinfunction "PA13_49") (pintype "bidirectional"))
    )
    (net (code "86") (name "USART1_RX") (class "Default")
      (node (ref "R19") (pin "1") (pinfunction "1_1") (pintype "passive"))
      (node (ref "U10") (pin "1") (pinfunction "R_1") (pintype "output"))
      (node (ref "U3") (pin "23") (pinfunction "PC5_23") (pintype "bidirectional"))
    )
    (net (code "87") (name "USART1_TX") (class "Default")
      (node (ref "U10") (pin "4") (pinfunction "D_4") (pintype "input"))
      (node (ref "U3") (pin "22") (pinfunction "PC4_22") (pintype "bidirectional"))
    )
    (net (code "88") (name "USART2_RX") (class "Default")
      (node (ref "J4") (pin "3") (pinfunction "3_3") (pintype "passive"))
      (node (ref "JP1") (pin "2") (pinfunction "2_2") (pintype "passive"))
      (node (ref "U3") (pin "17") (pinfunction "PA3_17") (pintype "bidirectional"))
    )
    (net (code "89") (name "USART2_TX") (class "Default")
      (node (ref "J4") (pin "2") (pinfunction "2_2") (pintype "passive"))
      (node (ref "JP1") (pin "1") (pinfunction "1_1") (pintype "passive"))
      (node (ref "U3") (pin "14") (pinfunction "PA2_14") (pintype "bidirectional"))
    )
    (net (code "90") (name "USART3_RX") (class "Default")
      (node (ref "U3") (pin "33") (pinfunction "PB11_33") (pintype "bidirectional"))
      (node (ref "U9") (pin "18") (pinfunction "TXD_18") (pintype "output"))
    )
    (net (code "91") (name "USART3_TX") (class "Default")
      (node (ref "U3") (pin "30") (pinfunction "PB10_30") (pintype "bidirectional"))
      (node (ref "U9") (pin "17") (pinfunction "RXD_17") (pintype "input"))
    )
    (net (code "92") (name "USB_DM") (class "Default")
      (node (ref "D8") (pin "4") (pinfunction "4_4") (pintype "passive"))
      (node (ref "J14") (pin "D-1") (pinfunction "D-_D-1") (pintype "bidirectional"))
      (node (ref "R4") (pin "1") (pinfunction "1_1") (pintype "passive"))
    )
    (net (code "93") (name "USB_DP") (class "Default")
      (node (ref "D8") (pin "3") (pinfunction "3_3") (pintype "passive"))
      (node (ref "J14") (pin "D+1") (pinfunction "D+_D+1") (pintype "bidirectional"))
      (node (ref "R5") (pin "1") (pinfunction "1_1") (pintype "passive"))
    )
    (net (code "94") (name "VDD") (class "Default")
      (node (ref "C1") (pin "1") (pinfunction "1_1") (pintype "passive"))
      (node (ref "C31") (pin "1") (pinfunction "1_1") (pintype "passive"))
      (node (ref "C32") (pin "1") (pinfunction "1_1") (pintype "passive"))
      (node (ref "C34") (pin "1") (pinfunction "1_1") (pintype "passive"))
      (node (ref "C37") (pin "1") (pinfunction "+_1") (pintype "passive"))
      (node (ref "C38") (pin "1") (pinfunction "1_1") (pintype "passive"))
      (node (ref "C39") (pin "1") (pinfunction "+_1") (pintype "passive"))
      (node (ref "C40") (pin "1") (pinfunction "1_1") (pintype "passive"))
      (node (ref "J1") (pin "2") (pinfunction "2_2") (pintype "passive"))
      (node (ref "Q1") (pin "5") (pinfunction "D_5") (pintype "passive"))
      (node (ref "Q1") (pin "6") (pinfunction "D_6") (pintype "passive"))
      (node (ref "Q1") (pin "7") (pinfunction "D_7") (pintype "passive"))
      (node (ref "Q1") (pin "8") (pinfunction "D_8") (pintype "passive"))
      (node (ref "Q1") (pin "9") (pinfunction "D_9") (pintype "passive"))
      (node (ref "Q4") (pin "5") (pinfunction "D_5") (pintype "passive"))
      (node (ref "Q4") (pin "6") (pinfunction "D_6") (pintype "passive"))
      (node (ref "Q4") (pin "7") (pinfunction "D_7") (pintype "passive"))
      (node (ref "Q4") (pin "8") (pinfunction "D_8") (pintype "passive"))
      (node (ref "Q4") (pin "9") (pinfunction "D_9") (pintype "passive"))
      (node (ref "TP10") (pin "1") (pinfunction "P$1_1") (pintype "bidirectional"))
      (node (ref "U1") (pin "6") (pinfunction "EN_6") (pintype "input"))
      (node (ref "U1") (pin "7") (pinfunction "VIN_7") (pintype "power_in"))
      (node (ref "U12") (pin "1") (pinfunction "VM_1") (pintype "power_in"))
    )
    (net (code "95") (name "unconnected-(J9-USBID-PadID1)") (class "Default")
      (node (ref "J9") (pin "ID1") (pinfunction "USBID_ID1") (pintype "bidirectional"))
    )
    (net (code "96") (name "unconnected-(J14-USBID-PadID1)") (class "Default")
      (node (ref "J14") (pin "ID1") (pinfunction "USBID_ID1") (pintype "bidirectional"))
    )
    (net (code "97") (name "unconnected-(U1-PG-Pad8)") (class "Default")
      (node (ref "U1") (pin "8") (pinfunction "PG_8") (pintype "open_collector"))
    )
    (net (code "98") (name "unconnected-(U3A-PA6-Pad20)") (class "Default")
      (node (ref "U3") (pin "20") (pinfunction "PA6_20") (pintype "bidirectional"))
    )
    (net (code "99") (name "unconnected-(U3A-PA7-Pad21)") (class "Default")
      (node (ref "U3") (pin "21") (pinfunction "PA7_21") (pintype "bidirectional"))
    )
    (net (code "100") (name "unconnected-(U3A-PA10-Pad44)") (class "Default")
      (node (ref "U3") (pin "44") (pinfunction "PA10_44") (pintype "bidirectional"))
    )
    (net (code "101") (name "unconnected-(U3A-PA15-Pad51)") (class "Default")
      (node (ref "U3") (pin "51") (pinfunction "PA15_51") (pintype "bidirectional"))
    )
    (net (code "102") (name "unconnected-(U3A-PB1-Pad25)") (class "Default")
      (node (ref "U3") (pin "25") (pinfunction "PB1_25") (pintype "bidirectional"))
    )
    (net (code "103") (name "unconnected-(U3A-PC0-Pad8)") (class "Default")
      (node (ref "U3") (pin "8") (pinfunction "PC0_8") (pintype "bidirectional"))
    )
    (net (code "104") (name "unconnected-(U6-NC-Pad7)") (class "Default")
      (node (ref "U6") (pin "7") (pinfunction "NC_7") (pintype "no_connect"))
    )
    (net (code "105") (name "unconnected-(U6-NC-Pad8)") (class "Default")
      (node (ref "U6") (pin "8") (pinfunction "NC_8") (pintype "no_connect"))
    )
    (net (code "106") (name "unconnected-(U6-NC-Pad9)") (class "Default")
      (node (ref "U6") (pin "9") (pinfunction "NC_9") (pintype "no_connect"))
    )
    (net (code "107") (name "unconnected-(U6-NC-Pad10)") (class "Default")
      (node (ref "U6") (pin "10") (pinfunction "NC_10") (pintype "no_connect"))
    )
    (net (code "108") (name "unconnected-(U9-GPIO.0{slash}CLK-Pad2)") (class "Default")
      (node (ref "U9") (pin "2") (pinfunction "GPIO.0/CLK_2") (pintype "bidirectional"))
    )
    (net (code "109") (name "unconnected-(U9-GPIO.1{slash}RS485-Pad1)") (class "Default")
      (node (ref "U9") (pin "1") (pinfunction "GPIO.1/RS485_1") (pintype "bidirectional"))
    )
    (net (code "110") (name "unconnected-(U9-GPIO.2{slash}TXT-Pad20)") (class "Default")
      (node (ref "U9") (pin "20") (pinfunction "GPIO.2/TXT_20") (pintype "bidirectional"))
    )
    (net (code "111") (name "unconnected-(U9-GPIO.3{slash}RXT-Pad19)") (class "Default")
      (node (ref "U9") (pin "19") (pinfunction "GPIO.3/RXT_19") (pintype "bidirectional"))
    )
    (net (code "112") (name "unconnected-(U9-NC-Pad10)") (class "Default")
      (node (ref "U9") (pin "10") (pinfunction "NC_10") (pintype "no_connect"))
    )
    (net (code "113") (name "unconnected-(U9-RTS-Pad16)") (class "Default")
      (node (ref "U9") (pin "16") (pinfunction "RTS_16") (pintype "output"))
    )
    (net (code "114") (name "unconnected-(U9-SUSPEND-Pad14)") (class "Default")
      (node (ref "U9") (pin "14") (pinfunction "SUSPEND_14") (pintype "output"))
    )
  )
)
